# 03-4G.net
KiCad netlist of a schematic drawn in Altium Designer
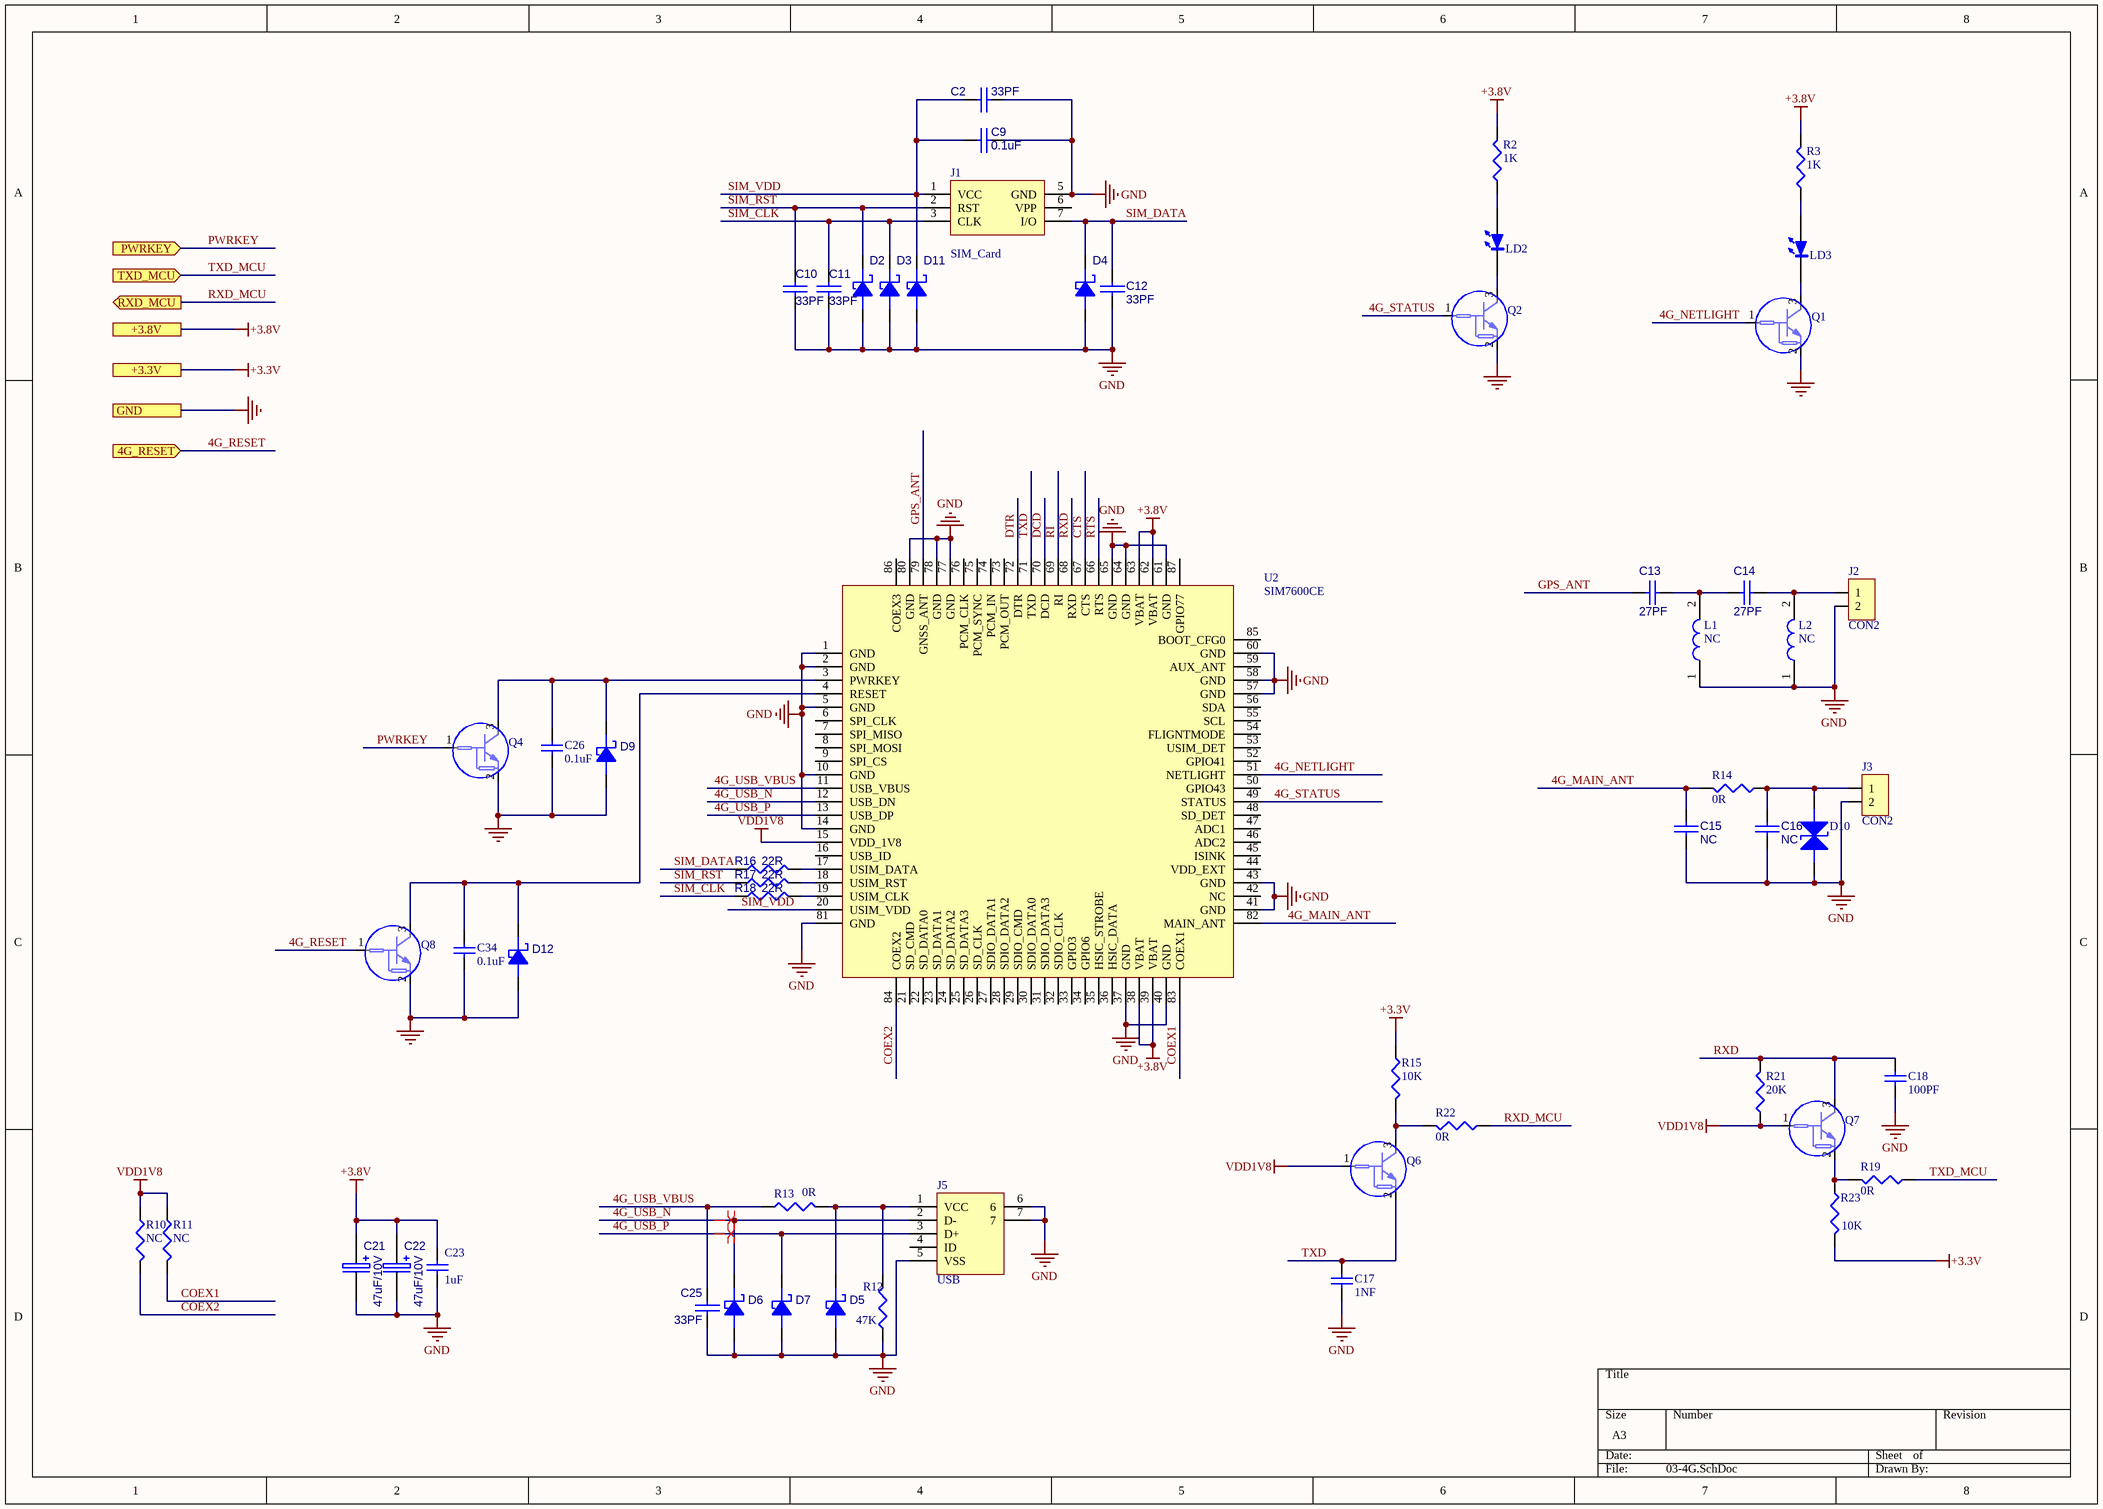
[diagram p0: 03-4G.SchDoc]

(export (version "E")
  (design (tool "Eeschema 10.0.6"))
  (components
    (comp (ref "C2")
      (value "33PF")
      (footprint "0603_C")
      (description "CAP")
      (libsource (lib "") (part "CAP_1"))
    )
    (comp (ref "C9")
      (value "0.1uF")
      (footprint "0603_C")
      (description "CAP")
      (libsource (lib "") (part "CAP_1"))
    )
    (comp (ref "C10")
      (value "33PF")
      (footprint "0603_C")
      (description "CAP")
      (libsource (lib "*") (part "CAP"))
    )
    (comp (ref "C11")
      (value "33PF")
      (footprint "0603_C")
      (description "CAP")
      (libsource (lib "*") (part "CAP"))
    )
    (comp (ref "C12")
      (value "33PF")
      (footprint "0603_C")
      (description "CAP")
      (libsource (lib "*") (part "CAP"))
    )
    (comp (ref "C13")
      (value "27PF")
      (footprint "0402")
      (description "CAP")
      (libsource (lib "") (part "CAP_1"))
    )
    (comp (ref "C14")
      (value "27PF")
      (footprint "0402")
      (description "CAP")
      (libsource (lib "") (part "CAP_1"))
    )
    (comp (ref "C15") (value "NC") (footprint "0402") (description "CAP") (libsource (lib "*") (part "CAP")))
    (comp (ref "C16") (value "NC") (footprint "0402") (description "CAP") (libsource (lib "*") (part "CAP")))
    (comp (ref "C17")
      (value "1NF")
      (footprint "0603_C")
      (description "Capacitor")
      (fields (field (name "PUBLISHER") "Altium Limited"))
      (libsource (lib "EP_MCB_V3.00") (part "Cap Semi"))
    )
    (comp (ref "C18")
      (value "100PF")
      (footprint "0603_C")
      (description "Capacitor")
      (fields (field (name "PUBLISHER") "Altium Limited"))
      (libsource (lib "EP_MCB_V3.00") (part "Cap Semi"))
    )
    (comp (ref "C21")
      (value "47uF/10V")
      (footprint "C_TAN_B")
      (description "E-CAP")
      (libsource (lib "*") (part "ECAP"))
    )
    (comp (ref "C22")
      (value "47uF/10V")
      (footprint "C_TAN_B")
      (description "E-CAP")
      (libsource (lib "*") (part "ECAP"))
    )
    (comp (ref "C23")
      (value "1uF")
      (footprint "0603_C")
      (description "Capacitor")
      (fields (field (name "PUBLISHER") "Altium Limited"))
      (libsource (lib "EP_MCB_V3.00") (part "Cap Semi"))
    )
    (comp (ref "C25")
      (value "33PF")
      (footprint "0603_C")
      (description "CAP")
      (libsource (lib "*") (part "CAP"))
    )
    (comp (ref "C26")
      (value "0.1uF")
      (footprint "0603_C")
      (description "Capacitor")
      (fields (field (name "PUBLISHER") "Altium Limited"))
      (libsource (lib "EP_MCB_V3.00") (part "Cap Semi"))
    )
    (comp (ref "C34")
      (value "0.1uF")
      (footprint "0603_C")
      (description "Capacitor")
      (fields (field (name "PUBLISHER") "Altium Limited"))
      (libsource (lib "EP_MCB_V3.00") (part "Cap Semi"))
    )
    (comp (ref "D2")
      (value "ESD9M5.0ST5G")
      (footprint "SOD-923")
      (libsource (lib "EP_MCB_V4.1") (part "DIODE SCHOTTKY"))
    )
    (comp (ref "D3")
      (value "ESD9M5.0ST5G")
      (footprint "SOD-923")
      (libsource (lib "EP_MCB_V4.1") (part "DIODE SCHOTTKY"))
    )
    (comp (ref "D4")
      (value "ESD9M5.0ST5G")
      (footprint "SOD-923")
      (libsource (lib "EP_MCB_V4.1") (part "DIODE SCHOTTKY"))
    )
    (comp (ref "D5")
      (value "PESD12VS1UB")
      (footprint "SOD523")
      (libsource (lib "EP_MCB_V4.1") (part "DIODE SCHOTTKY"))
    )
    (comp (ref "D6")
      (value "ESD9L5.0ST5G")
      (footprint "SOD-923")
      (libsource (lib "EP_MCB_V4.1") (part "DIODE SCHOTTKY"))
    )
    (comp (ref "D7")
      (value "ESD9L5.0ST5G")
      (footprint "SOD-923")
      (libsource (lib "EP_MCB_V4.1") (part "DIODE SCHOTTKY"))
    )
    (comp (ref "D9")
      (value "ESD9M5.0ST5G")
      (footprint "SOD-923")
      (libsource (lib "EP_MCB_V4.1") (part "DIODE SCHOTTKY"))
    )
    (comp (ref "D10")
      (value "LXES15AAA1-153")
      (footprint "0402")
      (libsource (lib "MySchlib") (part "DIODE TVS BI-DIR"))
    )
    (comp (ref "D11")
      (value "ESD9M5.0ST5G")
      (footprint "SOD-923")
      (libsource (lib "EP_MCB_V4.1") (part "DIODE SCHOTTKY"))
    )
    (comp (ref "D12")
      (value "ESD9M5.0ST5G")
      (footprint "SOD-923")
      (libsource (lib "EP_MCB_V4.1") (part "DIODE SCHOTTKY"))
    )
    (comp (ref "J1")
      (value "SIM_Card")
      (footprint "MicroSIM-6")
      (libsource (lib "MySchlib") (part "SIM_Card"))
    )
    (comp (ref "J2") (value "CON2") (footprint "RF-Z") (libsource (lib "MySchlib") (part "CON2")))
    (comp (ref "J3") (value "CON2") (footprint "RF-Z") (libsource (lib "MySchlib") (part "CON2")))
    (comp (ref "J5") (value "USB") (libsource (lib "MySchlib") (part "USB-M")))
    (comp (ref "L1") (value "NC") (footprint "0402") (libsource (lib "MySchlib") (part "L")))
    (comp (ref "L2") (value "NC") (footprint "0402") (libsource (lib "MySchlib") (part "L")))
    (comp (ref "LD2")
      (value "WHITE")
      (footprint "LED_0603")
      (description "LED")
      (libsource (lib "*") (part "LED"))
    )
    (comp (ref "LD3")
      (value "WHITE")
      (footprint "LED_0603")
      (description "LED")
      (libsource (lib "*") (part "LED"))
    )
    (comp (ref "Q1")
      (value "DTC143ZEBTL")
      (footprint "SC-85")
      (libsource (lib "MySchlib") (part "DTC143ZETL"))
    )
    (comp (ref "Q2")
      (value "DTC143ZEBTL")
      (footprint "SC-85")
      (libsource (lib "MySchlib") (part "DTC143ZETL"))
    )
    (comp (ref "Q4")
      (value "DTC143ZEBTL")
      (footprint "SC-85")
      (libsource (lib "MySchlib") (part "DTC143ZETL"))
    )
    (comp (ref "Q6")
      (value "DTC143ZEBTL")
      (footprint "SC-85")
      (libsource (lib "MySchlib") (part "DTC143ZETL"))
    )
    (comp (ref "Q7")
      (value "DTC143ZEBTL")
      (footprint "SC-85")
      (libsource (lib "MySchlib") (part "DTC143ZETL"))
    )
    (comp (ref "Q8")
      (value "DTC143ZEBTL")
      (footprint "SC-85")
      (libsource (lib "MySchlib") (part "DTC143ZETL"))
    )
    (comp (ref "R2") (value "1K") (footprint "0603_R") (libsource (lib "MySchlib") (part "RES1")))
    (comp (ref "R3") (value "1K") (footprint "0603_R") (libsource (lib "MySchlib") (part "RES1")))
    (comp (ref "R10") (value "NC") (footprint "0603_R") (libsource (lib "MySchlib") (part "RES1")))
    (comp (ref "R11") (value "NC") (footprint "0603_R") (libsource (lib "MySchlib") (part "RES1")))
    (comp (ref "R12") (value "47K") (footprint "0603_R") (libsource (lib "MySchlib") (part "RES1")))
    (comp (ref "R13") (value "0R") (footprint "0603_R") (libsource (lib "MySchlib") (part "RES1")))
    (comp (ref "R14") (value "0R") (footprint "0402") (libsource (lib "MySchlib") (part "RES1")))
    (comp (ref "R15") (value "10K") (footprint "0603_R") (libsource (lib "MySchlib") (part "RES1")))
    (comp (ref "R16")
      (value "22R")
      (footprint "0603_R")
      (description "RESISTOR")
      (libsource (lib "*") (part "R0.25W"))
    )
    (comp (ref "R17")
      (value "22R")
      (footprint "0603_R")
      (description "RESISTOR")
      (libsource (lib "*") (part "R0.25W"))
    )
    (comp (ref "R18")
      (value "22R")
      (footprint "0603_R")
      (description "RESISTOR")
      (libsource (lib "*") (part "R0.25W"))
    )
    (comp (ref "R19") (value "0R") (footprint "0603_R") (libsource (lib "MySchlib") (part "RES1")))
    (comp (ref "R21") (value "20K") (footprint "0603_R") (libsource (lib "MySchlib") (part "RES1")))
    (comp (ref "R22") (value "0R") (footprint "0603_R") (libsource (lib "MySchlib") (part "RES1")))
    (comp (ref "R23") (value "10K") (footprint "0603_R") (libsource (lib "MySchlib") (part "RES1")))
    (comp (ref "U2") (value "SIM7600CE") (footprint "SIM7600") (libsource (lib "MySchlib") (part "SIM7600")))
  )
  (nets
    (net (code "1") (name "+3.3V") (class "Default")
      (node (ref "R15") (pin "1") (pinfunction "1_1") (pintype "passive"))
      (node (ref "R23") (pin "2") (pinfunction "2_2") (pintype "passive"))
    )
    (net (code "2") (name "+3.8V") (class "Default")
      (node (ref "C21") (pin "1") (pinfunction "+_1") (pintype "passive"))
      (node (ref "C22") (pin "1") (pinfunction "+_1") (pintype "passive"))
      (node (ref "C23") (pin "2") (pinfunction "2_2") (pintype "passive"))
      (node (ref "R2") (pin "1") (pinfunction "1_1") (pintype "passive"))
      (node (ref "R3") (pin "1") (pinfunction "1_1") (pintype "passive"))
      (node (ref "U2") (pin "38") (pinfunction "VBAT_38") (pintype "passive"))
      (node (ref "U2") (pin "39") (pinfunction "VBAT_39") (pintype "passive"))
      (node (ref "U2") (pin "62") (pinfunction "VBAT_62") (pintype "passive"))
      (node (ref "U2") (pin "63") (pinfunction "VBAT_63") (pintype "passive"))
    )
    (net (code "3") (name "/4G_MAIN_ANT") (class "Default")
      (node (ref "C15") (pin "2") (pinfunction "2_2") (pintype "passive"))
      (node (ref "R14") (pin "2") (pinfunction "2_2") (pintype "passive"))
      (node (ref "U2") (pin "82") (pinfunction "MAIN_ANT_82") (pintype "passive"))
    )
    (net (code "4") (name "/4G_NETLIGHT") (class "Default")
      (node (ref "Q1") (pin "1") (pinfunction "B_1") (pintype "passive"))
      (node (ref "U2") (pin "51") (pinfunction "NETLIGHT_51") (pintype "passive"))
    )
    (net (code "5") (name "/4G_RESET") (class "Default")
      (node (ref "Q8") (pin "1") (pinfunction "B_1") (pintype "passive"))
    )
    (net (code "6") (name "/4G_STATUS") (class "Default")
      (node (ref "Q2") (pin "1") (pinfunction "B_1") (pintype "passive"))
      (node (ref "U2") (pin "49") (pinfunction "STATUS_49") (pintype "passive"))
    )
    (net (code "7") (name "/4G_USB_N") (class "Default")
      (node (ref "D6") (pin "2") (pinfunction "CATHODE_2") (pintype "passive"))
      (node (ref "J5") (pin "2") (pinfunction "D-_2") (pintype "passive"))
      (node (ref "U2") (pin "12") (pinfunction "USB_DN_12") (pintype "passive"))
    )
    (net (code "8") (name "/4G_USB_P") (class "Default")
      (node (ref "D7") (pin "2") (pinfunction "CATHODE_2") (pintype "passive"))
      (node (ref "J5") (pin "3") (pinfunction "D+_3") (pintype "passive"))
      (node (ref "U2") (pin "13") (pinfunction "USB_DP_13") (pintype "passive"))
    )
    (net (code "9") (name "/4G_USB_VBUS") (class "Default")
      (node (ref "C25") (pin "1") (pinfunction "1_1") (pintype "passive"))
      (node (ref "R13") (pin "1") (pinfunction "1_1") (pintype "passive"))
      (node (ref "U2") (pin "11") (pinfunction "USB_VBUS_11") (pintype "passive"))
    )
    (net (code "10") (name "/COEX1") (class "Default")
      (node (ref "R11") (pin "2") (pinfunction "2_2") (pintype "passive"))
      (node (ref "U2") (pin "83") (pinfunction "COEX1_83") (pintype "passive"))
    )
    (net (code "11") (name "/COEX2") (class "Default")
      (node (ref "R10") (pin "2") (pinfunction "2_2") (pintype "passive"))
      (node (ref "U2") (pin "84") (pinfunction "COEX2_84") (pintype "passive"))
    )
    (net (code "12") (name "/CTS") (class "Default")
      (node (ref "U2") (pin "67") (pinfunction "CTS_67") (pintype "passive"))
    )
    (net (code "13") (name "/DCD") (class "Default")
      (node (ref "U2") (pin "70") (pinfunction "DCD_70") (pintype "passive"))
    )
    (net (code "14") (name "/DTR") (class "Default")
      (node (ref "U2") (pin "72") (pinfunction "DTR_72") (pintype "passive"))
    )
    (net (code "15") (name "/GPS_ANT") (class "Default")
      (node (ref "C13") (pin "1") (pinfunction "1_1") (pintype "passive"))
      (node (ref "U2") (pin "79") (pinfunction "GNSS_ANT_79") (pintype "passive"))
    )
    (net (code "16") (name "/PWRKEY") (class "Default")
      (node (ref "Q4") (pin "1") (pinfunction "B_1") (pintype "passive"))
    )
    (net (code "17") (name "/RI") (class "Default")
      (node (ref "U2") (pin "69") (pinfunction "RI_69") (pintype "passive"))
    )
    (net (code "18") (name "/RTS") (class "Default")
      (node (ref "U2") (pin "66") (pinfunction "RTS_66") (pintype "passive"))
    )
    (net (code "19") (name "/RXD") (class "Default")
      (node (ref "C18") (pin "2") (pinfunction "2_2") (pintype "passive"))
      (node (ref "Q7") (pin "3") (pinfunction "C_3") (pintype "passive"))
      (node (ref "R21") (pin "2") (pinfunction "2_2") (pintype "passive"))
      (node (ref "U2") (pin "68") (pinfunction "RXD_68") (pintype "passive"))
    )
    (net (code "20") (name "/RXD_MCU") (class "Default")
      (node (ref "R22") (pin "1") (pinfunction "1_1") (pintype "passive"))
    )
    (net (code "21") (name "/SIM_CLK") (class "Default")
      (node (ref "C11") (pin "2") (pinfunction "2_2") (pintype "passive"))
      (node (ref "D3") (pin "2") (pinfunction "CATHODE_2") (pintype "passive"))
      (node (ref "J1") (pin "3") (pinfunction "CLK_3") (pintype "passive"))
      (node (ref "R18") (pin "1") (pinfunction "1_1") (pintype "passive"))
    )
    (net (code "22") (name "/SIM_DATA") (class "Default")
      (node (ref "C12") (pin "2") (pinfunction "2_2") (pintype "passive"))
      (node (ref "D4") (pin "2") (pinfunction "CATHODE_2") (pintype "passive"))
      (node (ref "J1") (pin "7") (pinfunction "I/O_7") (pintype "passive"))
      (node (ref "R16") (pin "1") (pinfunction "1_1") (pintype "passive"))
    )
    (net (code "23") (name "/SIM_RST") (class "Default")
      (node (ref "C10") (pin "2") (pinfunction "2_2") (pintype "passive"))
      (node (ref "D2") (pin "2") (pinfunction "CATHODE_2") (pintype "passive"))
      (node (ref "J1") (pin "2") (pinfunction "RST_2") (pintype "passive"))
      (node (ref "R17") (pin "1") (pinfunction "1_1") (pintype "passive"))
    )
    (net (code "24") (name "/SIM_VDD") (class "Default")
      (node (ref "C2") (pin "1") (pinfunction "1_1") (pintype "passive"))
      (node (ref "C9") (pin "1") (pinfunction "1_1") (pintype "passive"))
      (node (ref "D11") (pin "2") (pinfunction "CATHODE_2") (pintype "passive"))
      (node (ref "J1") (pin "1") (pinfunction "VCC_1") (pintype "passive"))
      (node (ref "U2") (pin "20") (pinfunction "USIM_VDD_20") (pintype "passive"))
    )
    (net (code "25") (name "/TXD") (class "Default")
      (node (ref "C17") (pin "1") (pinfunction "1_1") (pintype "passive"))
      (node (ref "Q6") (pin "2") (pinfunction "E_2") (pintype "passive"))
      (node (ref "U2") (pin "71") (pinfunction "TXD_71") (pintype "passive"))
    )
    (net (code "26") (name "/TXD_MCU") (class "Default")
      (node (ref "R19") (pin "1") (pinfunction "1_1") (pintype "passive"))
    )
    (net (code "27") (name "GND") (class "Default")
      (node (ref "C10") (pin "1") (pinfunction "1_1") (pintype "passive"))
      (node (ref "C11") (pin "1") (pinfunction "1_1") (pintype "passive"))
      (node (ref "C12") (pin "1") (pinfunction "1_1") (pintype "passive"))
      (node (ref "C15") (pin "1") (pinfunction "1_1") (pintype "passive"))
      (node (ref "C16") (pin "1") (pinfunction "1_1") (pintype "passive"))
      (node (ref "C17") (pin "2") (pinfunction "2_2") (pintype "passive"))
      (node (ref "C18") (pin "1") (pinfunction "1_1") (pintype "passive"))
      (node (ref "C2") (pin "2") (pinfunction "2_2") (pintype "passive"))
      (node (ref "C21") (pin "2") (pinfunction "-_2") (pintype "passive"))
      (node (ref "C22") (pin "2") (pinfunction "-_2") (pintype "passive"))
      (node (ref "C23") (pin "1") (pinfunction "1_1") (pintype "passive"))
      (node (ref "C25") (pin "2") (pinfunction "2_2") (pintype "passive"))
      (node (ref "C26") (pin "1") (pinfunction "1_1") (pintype "passive"))
      (node (ref "C34") (pin "1") (pinfunction "1_1") (pintype "passive"))
      (node (ref "C9") (pin "2") (pinfunction "2_2") (pintype "passive"))
      (node (ref "D10") (pin "2") (pinfunction "2_2") (pintype "passive"))
      (node (ref "D11") (pin "1") (pinfunction "ANODE_1") (pintype "passive"))
      (node (ref "D12") (pin "1") (pinfunction "ANODE_1") (pintype "passive"))
      (node (ref "D2") (pin "1") (pinfunction "ANODE_1") (pintype "passive"))
      (node (ref "D3") (pin "1") (pinfunction "ANODE_1") (pintype "passive"))
      (node (ref "D4") (pin "1") (pinfunction "ANODE_1") (pintype "passive"))
      (node (ref "D5") (pin "1") (pinfunction "ANODE_1") (pintype "passive"))
      (node (ref "D6") (pin "1") (pinfunction "ANODE_1") (pintype "passive"))
      (node (ref "D7") (pin "1") (pinfunction "ANODE_1") (pintype "passive"))
      (node (ref "D9") (pin "1") (pinfunction "ANODE_1") (pintype "passive"))
      (node (ref "J1") (pin "5") (pinfunction "GND_5") (pintype "passive"))
      (node (ref "J2") (pin "2") (pinfunction "2_2") (pintype "passive"))
      (node (ref "J3") (pin "2") (pinfunction "2_2") (pintype "passive"))
      (node (ref "J5") (pin "5") (pinfunction "VSS_5") (pintype "passive"))
      (node (ref "J5") (pin "6") (pinfunction "6_6") (pintype "passive"))
      (node (ref "J5") (pin "7") (pinfunction "7_7") (pintype "passive"))
      (node (ref "L1") (pin "1") (pinfunction "1_1") (pintype "passive"))
      (node (ref "L2") (pin "1") (pinfunction "1_1") (pintype "passive"))
      (node (ref "Q1") (pin "2") (pinfunction "E_2") (pintype "passive"))
      (node (ref "Q2") (pin "2") (pinfunction "E_2") (pintype "passive"))
      (node (ref "Q4") (pin "2") (pinfunction "E_2") (pintype "passive"))
      (node (ref "Q8") (pin "2") (pinfunction "E_2") (pintype "passive"))
      (node (ref "R12") (pin "2") (pinfunction "2_2") (pintype "passive"))
      (node (ref "U2") (pin "1") (pinfunction "GND_1") (pintype "passive"))
      (node (ref "U2") (pin "10") (pinfunction "GND_10") (pintype "passive"))
      (node (ref "U2") (pin "14") (pinfunction "GND_14") (pintype "passive"))
      (node (ref "U2") (pin "2") (pinfunction "GND_2") (pintype "passive"))
      (node (ref "U2") (pin "37") (pinfunction "GND_37") (pintype "passive"))
      (node (ref "U2") (pin "40") (pinfunction "GND_40") (pintype "passive"))
      (node (ref "U2") (pin "41") (pinfunction "GND_41") (pintype "passive"))
      (node (ref "U2") (pin "43") (pinfunction "GND_43") (pintype "passive"))
      (node (ref "U2") (pin "5") (pinfunction "GND_5") (pintype "passive"))
      (node (ref "U2") (pin "57") (pinfunction "GND_57") (pintype "passive"))
      (node (ref "U2") (pin "58") (pinfunction "GND_58") (pintype "passive"))
      (node (ref "U2") (pin "60") (pinfunction "GND_60") (pintype "passive"))
      (node (ref "U2") (pin "61") (pinfunction "GND_61") (pintype "passive"))
      (node (ref "U2") (pin "64") (pinfunction "GND_64") (pintype "passive"))
      (node (ref "U2") (pin "65") (pinfunction "GND_65") (pintype "passive"))
      (node (ref "U2") (pin "77") (pinfunction "GND_77") (pintype "passive"))
      (node (ref "U2") (pin "78") (pinfunction "GND_78") (pintype "passive"))
      (node (ref "U2") (pin "80") (pinfunction "GND_80") (pintype "passive"))
      (node (ref "U2") (pin "81") (pinfunction "GND_81") (pintype "passive"))
    )
    (net (code "28") (name "Net-(C13-Pad2)") (class "Default")
      (node (ref "C13") (pin "2") (pinfunction "2_2") (pintype "passive"))
      (node (ref "C14") (pin "1") (pinfunction "1_1") (pintype "passive"))
      (node (ref "L1") (pin "2") (pinfunction "2_2") (pintype "passive"))
    )
    (net (code "29") (name "Net-(C14-Pad2)") (class "Default")
      (node (ref "C14") (pin "2") (pinfunction "2_2") (pintype "passive"))
      (node (ref "J2") (pin "1") (pinfunction "1_1") (pintype "passive"))
      (node (ref "L2") (pin "2") (pinfunction "2_2") (pintype "passive"))
    )
    (net (code "30") (name "Net-(C16-Pad2)") (class "Default")
      (node (ref "C16") (pin "2") (pinfunction "2_2") (pintype "passive"))
      (node (ref "D10") (pin "1") (pinfunction "1_1") (pintype "passive"))
      (node (ref "J3") (pin "1") (pinfunction "1_1") (pintype "passive"))
      (node (ref "R14") (pin "1") (pinfunction "1_1") (pintype "passive"))
    )
    (net (code "31") (name "Net-(D5-CATHODE)") (class "Default")
      (node (ref "D5") (pin "2") (pinfunction "CATHODE_2") (pintype "passive"))
      (node (ref "J5") (pin "1") (pinfunction "VCC_1") (pintype "passive"))
      (node (ref "R12") (pin "1") (pinfunction "1_1") (pintype "passive"))
      (node (ref "R13") (pin "2") (pinfunction "2_2") (pintype "passive"))
    )
    (net (code "32") (name "Net-(D9-CATHODE)") (class "Default")
      (node (ref "C26") (pin "2") (pinfunction "2_2") (pintype "passive"))
      (node (ref "D9") (pin "2") (pinfunction "CATHODE_2") (pintype "passive"))
      (node (ref "Q4") (pin "3") (pinfunction "C_3") (pintype "passive"))
      (node (ref "U2") (pin "3") (pinfunction "PWRKEY_3") (pintype "passive"))
    )
    (net (code "33") (name "Net-(D12-CATHODE)") (class "Default")
      (node (ref "C34") (pin "2") (pinfunction "2_2") (pintype "passive"))
      (node (ref "D12") (pin "2") (pinfunction "CATHODE_2") (pintype "passive"))
      (node (ref "Q8") (pin "3") (pinfunction "C_3") (pintype "passive"))
      (node (ref "U2") (pin "4") (pinfunction "RESET_4") (pintype "passive"))
    )
    (net (code "34") (name "Net-(LD2-PadA)") (class "Default")
      (node (ref "LD2") (pin "A") (pinfunction "A_A") (pintype "passive"))
      (node (ref "R2") (pin "2") (pinfunction "2_2") (pintype "passive"))
    )
    (net (code "35") (name "Net-(LD3-PadA)") (class "Default")
      (node (ref "LD3") (pin "A") (pinfunction "A_A") (pintype "passive"))
      (node (ref "R3") (pin "2") (pinfunction "2_2") (pintype "passive"))
    )
    (net (code "36") (name "Net-(Q1-C)") (class "Default")
      (node (ref "LD3") (pin "K") (pinfunction "K_K") (pintype "passive"))
      (node (ref "Q1") (pin "3") (pinfunction "C_3") (pintype "passive"))
    )
    (net (code "37") (name "Net-(Q2-C)") (class "Default")
      (node (ref "LD2") (pin "K") (pinfunction "K_K") (pintype "passive"))
      (node (ref "Q2") (pin "3") (pinfunction "C_3") (pintype "passive"))
    )
    (net (code "38") (name "Net-(Q6-C)") (class "Default")
      (node (ref "Q6") (pin "3") (pinfunction "C_3") (pintype "passive"))
      (node (ref "R15") (pin "2") (pinfunction "2_2") (pintype "passive"))
      (node (ref "R22") (pin "2") (pinfunction "2_2") (pintype "passive"))
    )
    (net (code "39") (name "Net-(Q7-E)") (class "Default")
      (node (ref "Q7") (pin "2") (pinfunction "E_2") (pintype "passive"))
      (node (ref "R19") (pin "2") (pinfunction "2_2") (pintype "passive"))
      (node (ref "R23") (pin "1") (pinfunction "1_1") (pintype "passive"))
    )
    (net (code "40") (name "Net-(U2-USIM_CLK)") (class "Default")
      (node (ref "R18") (pin "2") (pinfunction "2_2") (pintype "passive"))
      (node (ref "U2") (pin "19") (pinfunction "USIM_CLK_19") (pintype "passive"))
    )
    (net (code "41") (name "Net-(U2-USIM_DATA)") (class "Default")
      (node (ref "R16") (pin "2") (pinfunction "2_2") (pintype "passive"))
      (node (ref "U2") (pin "17") (pinfunction "USIM_DATA_17") (pintype "passive"))
    )
    (net (code "42") (name "Net-(U2-USIM_RST)") (class "Default")
      (node (ref "R17") (pin "2") (pinfunction "2_2") (pintype "passive"))
      (node (ref "U2") (pin "18") (pinfunction "USIM_RST_18") (pintype "passive"))
    )
    (net (code "43") (name "VDD1V8") (class "Default")
      (node (ref "Q6") (pin "1") (pinfunction "B_1") (pintype "passive"))
      (node (ref "Q7") (pin "1") (pinfunction "B_1") (pintype "passive"))
      (node (ref "R10") (pin "1") (pinfunction "1_1") (pintype "passive"))
      (node (ref "R11") (pin "1") (pinfunction "1_1") (pintype "passive"))
      (node (ref "R21") (pin "1") (pinfunction "1_1") (pintype "passive"))
      (node (ref "U2") (pin "15") (pinfunction "VDD_1V8_15") (pintype "passive"))
    )
    (net (code "44") (name "unconnected-(J1-VPP-Pad6)") (class "Default")
      (node (ref "J1") (pin "6") (pinfunction "VPP_6") (pintype "passive"))
    )
    (net (code "45") (name "unconnected-(J5-ID-Pad4)") (class "Default")
      (node (ref "J5") (pin "4") (pinfunction "ID_4") (pintype "passive"))
    )
    (net (code "46") (name "unconnected-(U2-ADC1-Pad47)") (class "Default")
      (node (ref "U2") (pin "47") (pinfunction "ADC1_47") (pintype "passive"))
    )
    (net (code "47") (name "unconnected-(U2-ADC2-Pad46)") (class "Default")
      (node (ref "U2") (pin "46") (pinfunction "ADC2_46") (pintype "passive"))
    )
    (net (code "48") (name "unconnected-(U2-AUX_ANT-Pad59)") (class "Default")
      (node (ref "U2") (pin "59") (pinfunction "AUX_ANT_59") (pintype "passive"))
    )
    (net (code "49") (name "unconnected-(U2-BOOT_CFG0-Pad85)") (class "Default")
      (node (ref "U2") (pin "85") (pinfunction "BOOT_CFG0_85") (pintype "passive"))
    )
    (net (code "50") (name "unconnected-(U2-COEX3-Pad86)") (class "Default")
      (node (ref "U2") (pin "86") (pinfunction "COEX3_86") (pintype "passive"))
    )
    (net (code "51") (name "unconnected-(U2-FLIGNTMODE-Pad54)") (class "Default")
      (node (ref "U2") (pin "54") (pinfunction "FLIGNTMODE_54") (pintype "passive"))
    )
    (net (code "52") (name "unconnected-(U2-GPIO3-Pad33)") (class "Default")
      (node (ref "U2") (pin "33") (pinfunction "GPIO3_33") (pintype "passive"))
    )
    (net (code "53") (name "unconnected-(U2-GPIO6-Pad34)") (class "Default")
      (node (ref "U2") (pin "34") (pinfunction "GPIO6_34") (pintype "passive"))
    )
    (net (code "54") (name "unconnected-(U2-GPIO41-Pad52)") (class "Default")
      (node (ref "U2") (pin "52") (pinfunction "GPIO41_52") (pintype "passive"))
    )
    (net (code "55") (name "unconnected-(U2-GPIO43-Pad50)") (class "Default")
      (node (ref "U2") (pin "50") (pinfunction "GPIO43_50") (pintype "passive"))
    )
    (net (code "56") (name "unconnected-(U2-GPIO77-Pad87)") (class "Default")
      (node (ref "U2") (pin "87") (pinfunction "GPIO77_87") (pintype "passive"))
    )
    (net (code "57") (name "unconnected-(U2-HSIC_DATA-Pad36)") (class "Default")
      (node (ref "U2") (pin "36") (pinfunction "HSIC_DATA_36") (pintype "passive"))
    )
    (net (code "58") (name "unconnected-(U2-HSIC_STROBE-Pad35)") (class "Default")
      (node (ref "U2") (pin "35") (pinfunction "HSIC_STROBE_35") (pintype "passive"))
    )
    (net (code "59") (name "unconnected-(U2-ISINK-Pad45)") (class "Default")
      (node (ref "U2") (pin "45") (pinfunction "ISINK_45") (pintype "passive"))
    )
    (net (code "60") (name "unconnected-(U2-NC-Pad42)") (class "Default")
      (node (ref "U2") (pin "42") (pinfunction "NC_42") (pintype "passive"))
    )
    (net (code "61") (name "unconnected-(U2-PCM_CLK-Pad76)") (class "Default")
      (node (ref "U2") (pin "76") (pinfunction "PCM_CLK_76") (pintype "passive"))
    )
    (net (code "62") (name "unconnected-(U2-PCM_IN-Pad74)") (class "Default")
      (node (ref "U2") (pin "74") (pinfunction "PCM_IN_74") (pintype "passive"))
    )
    (net (code "63") (name "unconnected-(U2-PCM_OUT-Pad73)") (class "Default")
      (node (ref "U2") (pin "73") (pinfunction "PCM_OUT_73") (pintype "passive"))
    )
    (net (code "64") (name "unconnected-(U2-PCM_SYNC-Pad75)") (class "Default")
      (node (ref "U2") (pin "75") (pinfunction "PCM_SYNC_75") (pintype "passive"))
    )
    (net (code "65") (name "unconnected-(U2-SCL-Pad55)") (class "Default")
      (node (ref "U2") (pin "55") (pinfunction "SCL_55") (pintype "passive"))
    )
    (net (code "66") (name "unconnected-(U2-SDA-Pad56)") (class "Default")
      (node (ref "U2") (pin "56") (pinfunction "SDA_56") (pintype "passive"))
    )
    (net (code "67") (name "unconnected-(U2-SDIO_CLK-Pad32)") (class "Default")
      (node (ref "U2") (pin "32") (pinfunction "SDIO_CLK_32") (pintype "passive"))
    )
    (net (code "68") (name "unconnected-(U2-SDIO_CMD-Pad29)") (class "Default")
      (node (ref "U2") (pin "29") (pinfunction "SDIO_CMD_29") (pintype "passive"))
    )
    (net (code "69") (name "unconnected-(U2-SDIO_DATA0-Pad30)") (class "Default")
      (node (ref "U2") (pin "30") (pinfunction "SDIO_DATA0_30") (pintype "passive"))
    )
    (net (code "70") (name "unconnected-(U2-SDIO_DATA1-Pad27)") (class "Default")
      (node (ref "U2") (pin "27") (pinfunction "SDIO_DATA1_27") (pintype "passive"))
    )
    (net (code "71") (name "unconnected-(U2-SDIO_DATA2-Pad28)") (class "Default")
      (node (ref "U2") (pin "28") (pinfunction "SDIO_DATA2_28") (pintype "passive"))
    )
    (net (code "72") (name "unconnected-(U2-SDIO_DATA3-Pad31)") (class "Default")
      (node (ref "U2") (pin "31") (pinfunction "SDIO_DATA3_31") (pintype "passive"))
    )
    (net (code "73") (name "unconnected-(U2-SD_CLK-Pad26)") (class "Default")
      (node (ref "U2") (pin "26") (pinfunction "SD_CLK_26") (pintype "passive"))
    )
    (net (code "74") (name "unconnected-(U2-SD_CMD-Pad21)") (class "Default")
      (node (ref "U2") (pin "21") (pinfunction "SD_CMD_21") (pintype "passive"))
    )
    (net (code "75") (name "unconnected-(U2-SD_DATA0-Pad22)") (class "Default")
      (node (ref "U2") (pin "22") (pinfunction "SD_DATA0_22") (pintype "passive"))
    )
    (net (code "76") (name "unconnected-(U2-SD_DATA1-Pad23)") (class "Default")
      (node (ref "U2") (pin "23") (pinfunction "SD_DATA1_23") (pintype "passive"))
    )
    (net (code "77") (name "unconnected-(U2-SD_DATA2-Pad24)") (class "Default")
      (node (ref "U2") (pin "24") (pinfunction "SD_DATA2_24") (pintype "passive"))
    )
    (net (code "78") (name "unconnected-(U2-SD_DATA3-Pad25)") (class "Default")
      (node (ref "U2") (pin "25") (pinfunction "SD_DATA3_25") (pintype "passive"))
    )
    (net (code "79") (name "unconnected-(U2-SD_DET-Pad48)") (class "Default")
      (node (ref "U2") (pin "48") (pinfunction "SD_DET_48") (pintype "passive"))
    )
    (net (code "80") (name "unconnected-(U2-SPI_CLK-Pad6)") (class "Default")
      (node (ref "U2") (pin "6") (pinfunction "SPI_CLK_6") (pintype "passive"))
    )
    (net (code "81") (name "unconnected-(U2-SPI_CS-Pad9)") (class "Default")
      (node (ref "U2") (pin "9") (pinfunction "SPI_CS_9") (pintype "passive"))
    )
    (net (code "82") (name "unconnected-(U2-SPI_MISO-Pad7)") (class "Default")
      (node (ref "U2") (pin "7") (pinfunction "SPI_MISO_7") (pintype "passive"))
    )
    (net (code "83") (name "unconnected-(U2-SPI_MOSI-Pad8)") (class "Default")
      (node (ref "U2") (pin "8") (pinfunction "SPI_MOSI_8") (pintype "passive"))
    )
    (net (code "84") (name "unconnected-(U2-USB_ID-Pad16)") (class "Default")
      (node (ref "U2") (pin "16") (pinfunction "USB_ID_16") (pintype "passive"))
    )
    (net (code "85") (name "unconnected-(U2-USIM_DET-Pad53)") (class "Default")
      (node (ref "U2") (pin "53") (pinfunction "USIM_DET_53") (pintype "passive"))
    )
    (net (code "86") (name "unconnected-(U2-VDD_EXT-Pad44)") (class "Default")
      (node (ref "U2") (pin "44") (pinfunction "VDD_EXT_44") (pintype "passive"))
    )
  )
)
